# MKRSDProtoshield_Rev1_1.net
KiCad netlist of a schematic drawn in EAGLE
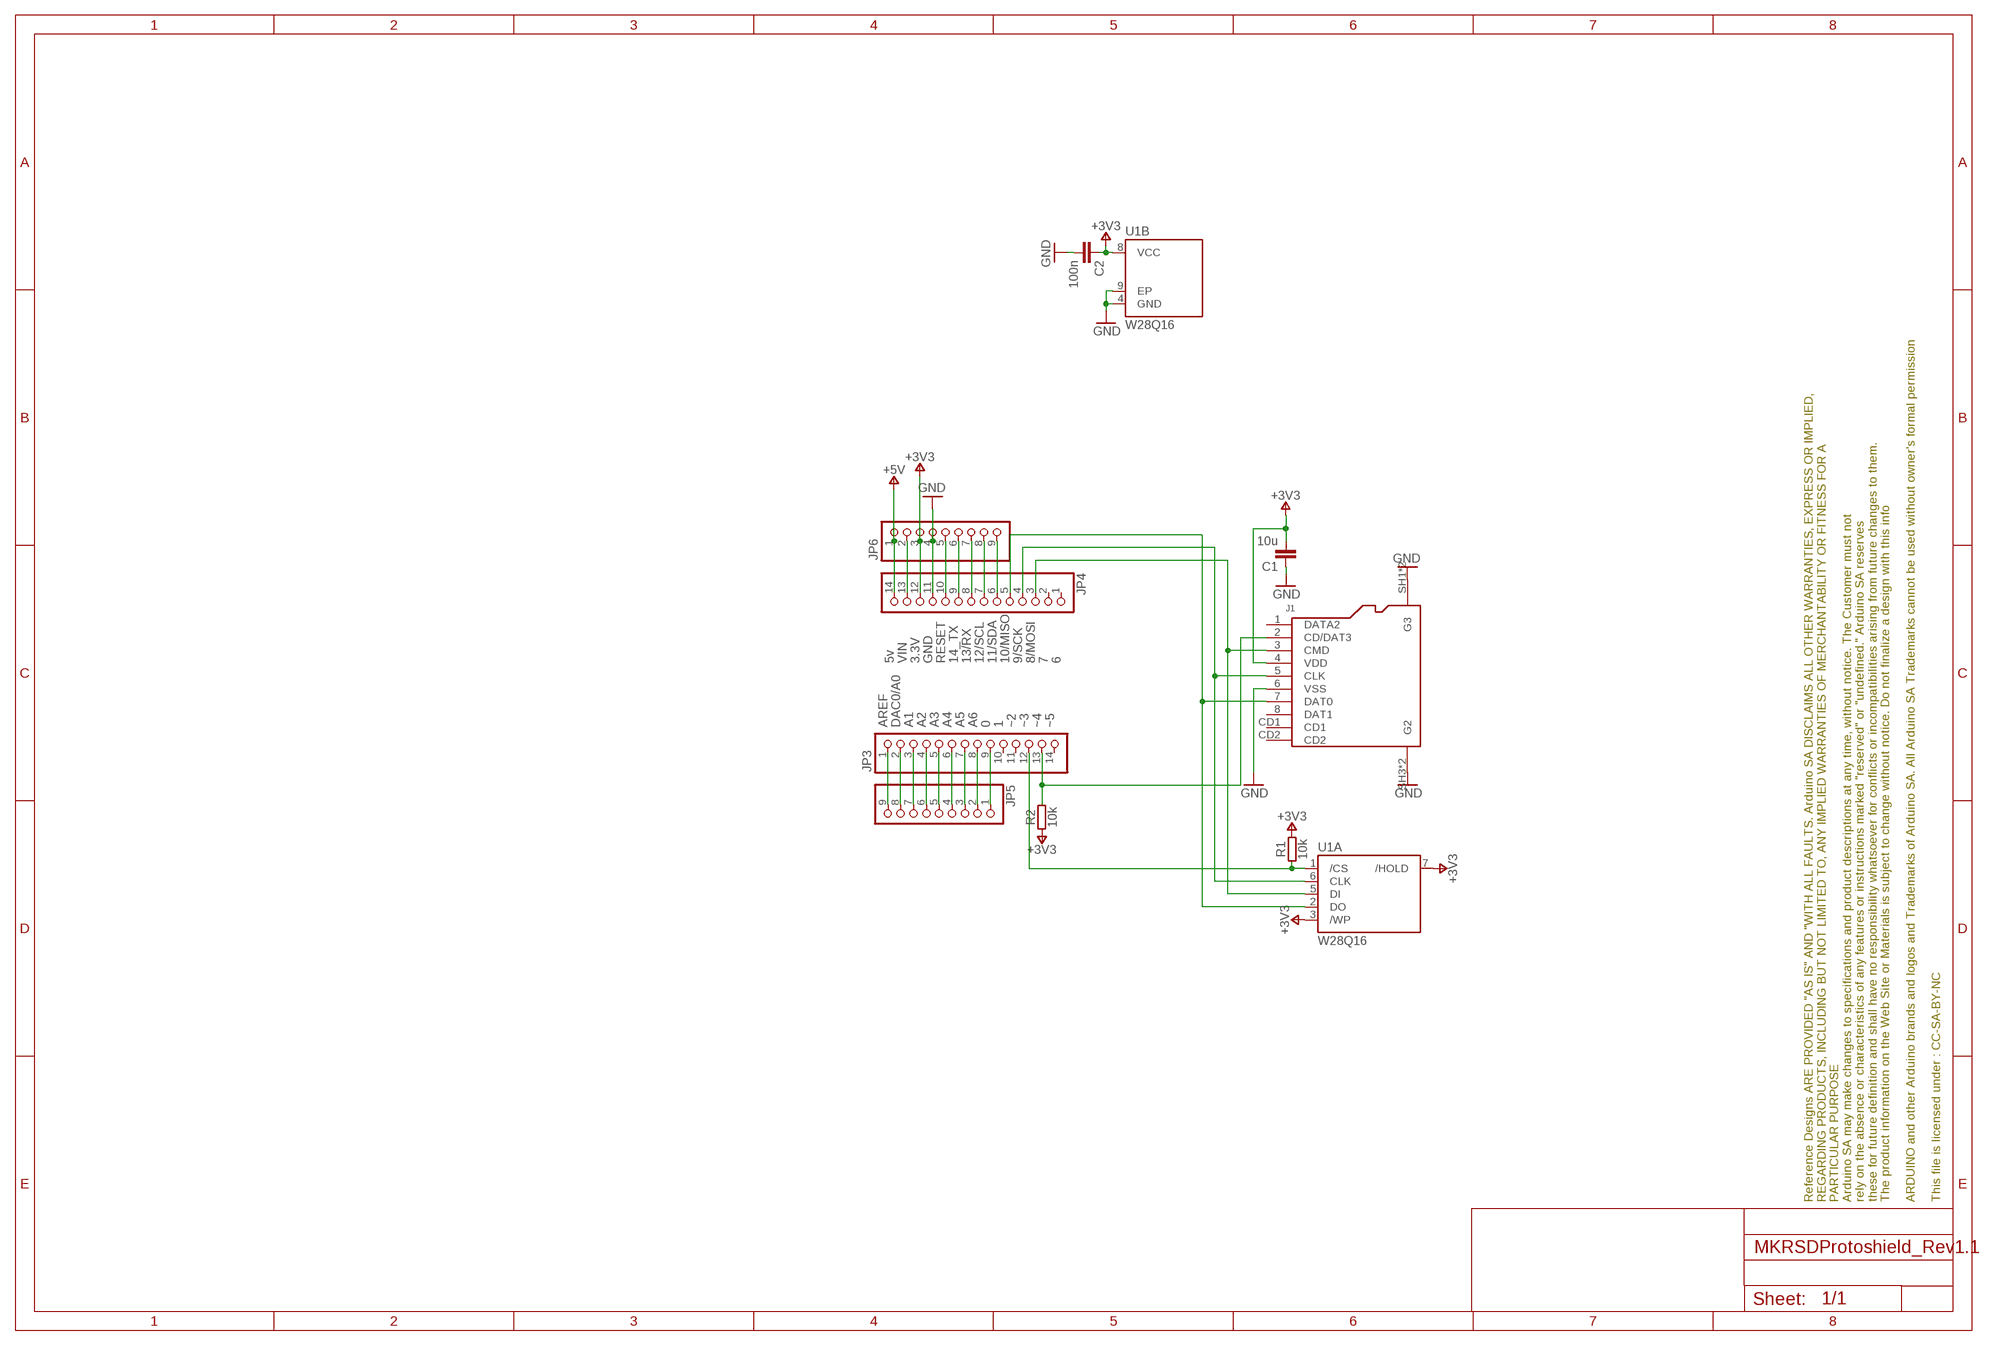
[diagram p0: schematic, sheet 1]

(export (version "E")
  (design (tool "Eeschema 10.0.6"))
  (components
    (comp (ref "C1")
      (value "10u")
      (footprint "eagle-import:0603-1608X90N")
      (fields (field (name "MANUFACTURER") "Murata"))
      (libsource (lib "eagle-import") (part "C-0603-10UF"))
    )
    (comp (ref "C2")
      (value "100n")
      (footprint "eagle-import:0603-1608X90N")
      (fields (field (name "MANUFACTURER") "Murata"))
      (libsource (lib "eagle-import") (part "C-0603-100NF"))
    )
    (comp (ref "FRAME1")
      (value "DNP")
      (footprint "eagle-import:FRAME")
      (libsource (lib "eagle-import") (part "A3-FRAME-STANDARD"))
    )
    (comp (ref "J1")
      (value "AMPHENOL_114-00841-68")
      (footprint "eagle-import:AMPHENOL_114-00841-68")
      (libsource (lib "eagle-import") (part "AMPHENOL_114-00841-68"))
    )
    (comp (ref "JP3")
      (value "-")
      (footprint "eagle-import:1X14")
      (fields (field (name "MANUFACTURER") "ELDECO"))
      (libsource (lib "eagle-import") (part "PINHD-1X14TH"))
    )
    (comp (ref "JP4")
      (value "-")
      (footprint "eagle-import:1X14")
      (fields (field (name "MANUFACTURER") "ELDECO"))
      (libsource (lib "eagle-import") (part "PINHD-1X14TH"))
    )
    (comp (ref "JP5")
      (value "PINHD-1X9")
      (footprint "eagle-import:1X09")
      (libsource (lib "eagle-import") (part "PINHD-1X9"))
    )
    (comp (ref "JP6")
      (value "PINHD-1X9")
      (footprint "eagle-import:1X09")
      (libsource (lib "eagle-import") (part "PINHD-1X9"))
    )
    (comp (ref "R1")
      (value "10k")
      (footprint "eagle-import:C0603")
      (fields (field (name "MANUFACTURER") "Yageo"))
      (libsource (lib "eagle-import") (part "R-0603-10K"))
    )
    (comp (ref "R2")
      (value "10k")
      (footprint "eagle-import:C0603")
      (fields (field (name "MANUFACTURER") "Yageo"))
      (libsource (lib "eagle-import") (part "R-0603-10K"))
    )
    (comp (ref "U1")
      (value "W28Q16")
      (footprint "eagle-import:SON9P127_500X600X80L60X41T340X400N")
      (fields (field (name "MANUFACTURER") "Winbond"))
      (libsource (lib "eagle-import") (part "W25QZP16DV?IG"))
    )
  )
  (nets
    (net (code "1") (name "+3V3") (class "Default")
      (node (ref "C1") (pin "2") (pinfunction "2_2") (pintype "passive"))
      (node (ref "C2") (pin "1") (pinfunction "1_1") (pintype "passive"))
      (node (ref "J1") (pin "4") (pinfunction "VDD_4") (pintype "power_in"))
      (node (ref "JP4") (pin "12") (pinfunction "12_12") (pintype "passive"))
      (node (ref "JP6") (pin "3") (pinfunction "3_3") (pintype "passive"))
      (node (ref "R1") (pin "2") (pinfunction "2_2") (pintype "passive"))
      (node (ref "R2") (pin "1") (pinfunction "1_1") (pintype "passive"))
      (node (ref "U1") (pin "3") (pinfunction "/WP_3") (pintype "input"))
      (node (ref "U1") (pin "7") (pinfunction "/HOLD_7") (pintype "input"))
      (node (ref "U1") (pin "8") (pinfunction "VCC_8") (pintype "power_in"))
    )
    (net (code "2") (name "+5V") (class "Default")
      (node (ref "JP4") (pin "14") (pinfunction "14_14") (pintype "passive"))
      (node (ref "JP6") (pin "1") (pinfunction "1_1") (pintype "passive"))
    )
    (net (code "3") (name "GND") (class "Default")
      (node (ref "C1") (pin "1") (pinfunction "1_1") (pintype "passive"))
      (node (ref "C2") (pin "2") (pinfunction "2_2") (pintype "passive"))
      (node (ref "J1") (pin "6") (pinfunction "VSS_6") (pintype "power_in"))
      (node (ref "J1") (pin "SH1") (pinfunction "G3_SH1") (pintype "bidirectional"))
      (node (ref "J1") (pin "SH2") (pinfunction "G3_SH2") (pintype "bidirectional"))
      (node (ref "J1") (pin "SH3") (pinfunction "G2_SH3") (pintype "bidirectional"))
      (node (ref "J1") (pin "SH4") (pinfunction "G2_SH4") (pintype "bidirectional"))
      (node (ref "JP4") (pin "11") (pinfunction "11_11") (pintype "passive"))
      (node (ref "JP6") (pin "4") (pinfunction "4_4") (pintype "passive"))
      (node (ref "U1") (pin "4") (pinfunction "GND_4") (pintype "power_in"))
      (node (ref "U1") (pin "9") (pinfunction "EP_9") (pintype "passive"))
    )
    (net (code "4") (name "Net-(J1-CD{slash}DAT3)") (class "Default")
      (node (ref "J1") (pin "2") (pinfunction "CD/DAT3_2") (pintype "bidirectional"))
      (node (ref "JP3") (pin "13") (pinfunction "13_13") (pintype "passive"))
      (node (ref "R2") (pin "2") (pinfunction "2_2") (pintype "passive"))
    )
    (net (code "5") (name "Net-(J1-CLK)") (class "Default")
      (node (ref "J1") (pin "5") (pinfunction "CLK_5") (pintype "bidirectional"))
      (node (ref "JP4") (pin "4") (pinfunction "4_4") (pintype "passive"))
      (node (ref "U1") (pin "6") (pinfunction "CLK_6") (pintype "input"))
    )
    (net (code "6") (name "Net-(J1-CMD)") (class "Default")
      (node (ref "J1") (pin "3") (pinfunction "CMD_3") (pintype "bidirectional"))
      (node (ref "JP4") (pin "3") (pinfunction "3_3") (pintype "passive"))
      (node (ref "U1") (pin "5") (pinfunction "DI_5") (pintype "input"))
    )
    (net (code "7") (name "Net-(J1-DAT0)") (class "Default")
      (node (ref "J1") (pin "7") (pinfunction "DAT0_7") (pintype "bidirectional"))
      (node (ref "JP4") (pin "5") (pinfunction "5_5") (pintype "passive"))
      (node (ref "U1") (pin "2") (pinfunction "DO_2") (pintype "tri_state"))
    )
    (net (code "8") (name "Net-(JP3-Pad1)") (class "Default")
      (node (ref "JP3") (pin "1") (pinfunction "1_1") (pintype "passive"))
      (node (ref "JP5") (pin "9") (pinfunction "9_9") (pintype "passive"))
    )
    (net (code "9") (name "Net-(JP3-Pad2)") (class "Default")
      (node (ref "JP3") (pin "2") (pinfunction "2_2") (pintype "passive"))
      (node (ref "JP5") (pin "8") (pinfunction "8_8") (pintype "passive"))
    )
    (net (code "10") (name "Net-(JP3-Pad3)") (class "Default")
      (node (ref "JP3") (pin "3") (pinfunction "3_3") (pintype "passive"))
      (node (ref "JP5") (pin "7") (pinfunction "7_7") (pintype "passive"))
    )
    (net (code "11") (name "Net-(JP3-Pad4)") (class "Default")
      (node (ref "JP3") (pin "4") (pinfunction "4_4") (pintype "passive"))
      (node (ref "JP5") (pin "6") (pinfunction "6_6") (pintype "passive"))
    )
    (net (code "12") (name "Net-(JP3-Pad5)") (class "Default")
      (node (ref "JP3") (pin "5") (pinfunction "5_5") (pintype "passive"))
      (node (ref "JP5") (pin "5") (pinfunction "5_5") (pintype "passive"))
    )
    (net (code "13") (name "Net-(JP3-Pad6)") (class "Default")
      (node (ref "JP3") (pin "6") (pinfunction "6_6") (pintype "passive"))
      (node (ref "JP5") (pin "4") (pinfunction "4_4") (pintype "passive"))
    )
    (net (code "14") (name "Net-(JP3-Pad7)") (class "Default")
      (node (ref "JP3") (pin "7") (pinfunction "7_7") (pintype "passive"))
      (node (ref "JP5") (pin "3") (pinfunction "3_3") (pintype "passive"))
    )
    (net (code "15") (name "Net-(JP3-Pad8)") (class "Default")
      (node (ref "JP3") (pin "8") (pinfunction "8_8") (pintype "passive"))
      (node (ref "JP5") (pin "2") (pinfunction "2_2") (pintype "passive"))
    )
    (net (code "16") (name "Net-(JP3-Pad9)") (class "Default")
      (node (ref "JP3") (pin "9") (pinfunction "9_9") (pintype "passive"))
      (node (ref "JP5") (pin "1") (pinfunction "1_1") (pintype "passive"))
    )
    (net (code "17") (name "Net-(JP4-Pad6)") (class "Default")
      (node (ref "JP4") (pin "6") (pinfunction "6_6") (pintype "passive"))
      (node (ref "JP6") (pin "9") (pinfunction "9_9") (pintype "passive"))
    )
    (net (code "18") (name "Net-(JP4-Pad7)") (class "Default")
      (node (ref "JP4") (pin "7") (pinfunction "7_7") (pintype "passive"))
      (node (ref "JP6") (pin "8") (pinfunction "8_8") (pintype "passive"))
    )
    (net (code "19") (name "Net-(JP4-Pad8)") (class "Default")
      (node (ref "JP4") (pin "8") (pinfunction "8_8") (pintype "passive"))
      (node (ref "JP6") (pin "7") (pinfunction "7_7") (pintype "passive"))
    )
    (net (code "20") (name "Net-(JP4-Pad9)") (class "Default")
      (node (ref "JP4") (pin "9") (pinfunction "9_9") (pintype "passive"))
      (node (ref "JP6") (pin "6") (pinfunction "6_6") (pintype "passive"))
    )
    (net (code "21") (name "Net-(JP4-Pad10)") (class "Default")
      (node (ref "JP4") (pin "10") (pinfunction "10_10") (pintype "passive"))
      (node (ref "JP6") (pin "5") (pinfunction "5_5") (pintype "passive"))
    )
    (net (code "22") (name "Net-(JP4-Pad13)") (class "Default")
      (node (ref "JP4") (pin "13") (pinfunction "13_13") (pintype "passive"))
      (node (ref "JP6") (pin "2") (pinfunction "2_2") (pintype "passive"))
    )
    (net (code "23") (name "Net-(U1A-{slash}CS)") (class "Default")
      (node (ref "JP3") (pin "12") (pinfunction "12_12") (pintype "passive"))
      (node (ref "R1") (pin "1") (pinfunction "1_1") (pintype "passive"))
      (node (ref "U1") (pin "1") (pinfunction "/CS_1") (pintype "input"))
    )
    (net (code "24") (name "unconnected-(J1-DAT1-Pad8)") (class "Default")
      (node (ref "J1") (pin "8") (pinfunction "DAT1_8") (pintype "bidirectional"))
    )
    (net (code "25") (name "unconnected-(J1-DATA2-Pad1)") (class "Default")
      (node (ref "J1") (pin "1") (pinfunction "DATA2_1") (pintype "bidirectional"))
    )
    (net (code "26") (name "unconnected-(J1-PadCD1)") (class "Default")
      (node (ref "J1") (pin "CD1") (pinfunction "CD1_CD1") (pintype "bidirectional"))
    )
    (net (code "27") (name "unconnected-(J1-PadCD2)") (class "Default")
      (node (ref "J1") (pin "CD2") (pinfunction "CD2_CD2") (pintype "bidirectional"))
    )
    (net (code "28") (name "unconnected-(JP3-Pad10)") (class "Default")
      (node (ref "JP3") (pin "10") (pinfunction "10_10") (pintype "passive"))
    )
    (net (code "29") (name "unconnected-(JP3-Pad11)") (class "Default")
      (node (ref "JP3") (pin "11") (pinfunction "11_11") (pintype "passive"))
    )
    (net (code "30") (name "unconnected-(JP3-Pad14)") (class "Default")
      (node (ref "JP3") (pin "14") (pinfunction "14_14") (pintype "passive"))
    )
    (net (code "31") (name "unconnected-(JP4-Pad1)") (class "Default")
      (node (ref "JP4") (pin "1") (pinfunction "1_1") (pintype "passive"))
    )
    (net (code "32") (name "unconnected-(JP4-Pad2)") (class "Default")
      (node (ref "JP4") (pin "2") (pinfunction "2_2") (pintype "passive"))
    )
  )
)
